# Hardwiring.net
KiCad netlist of a schematic drawn in Altium Designer
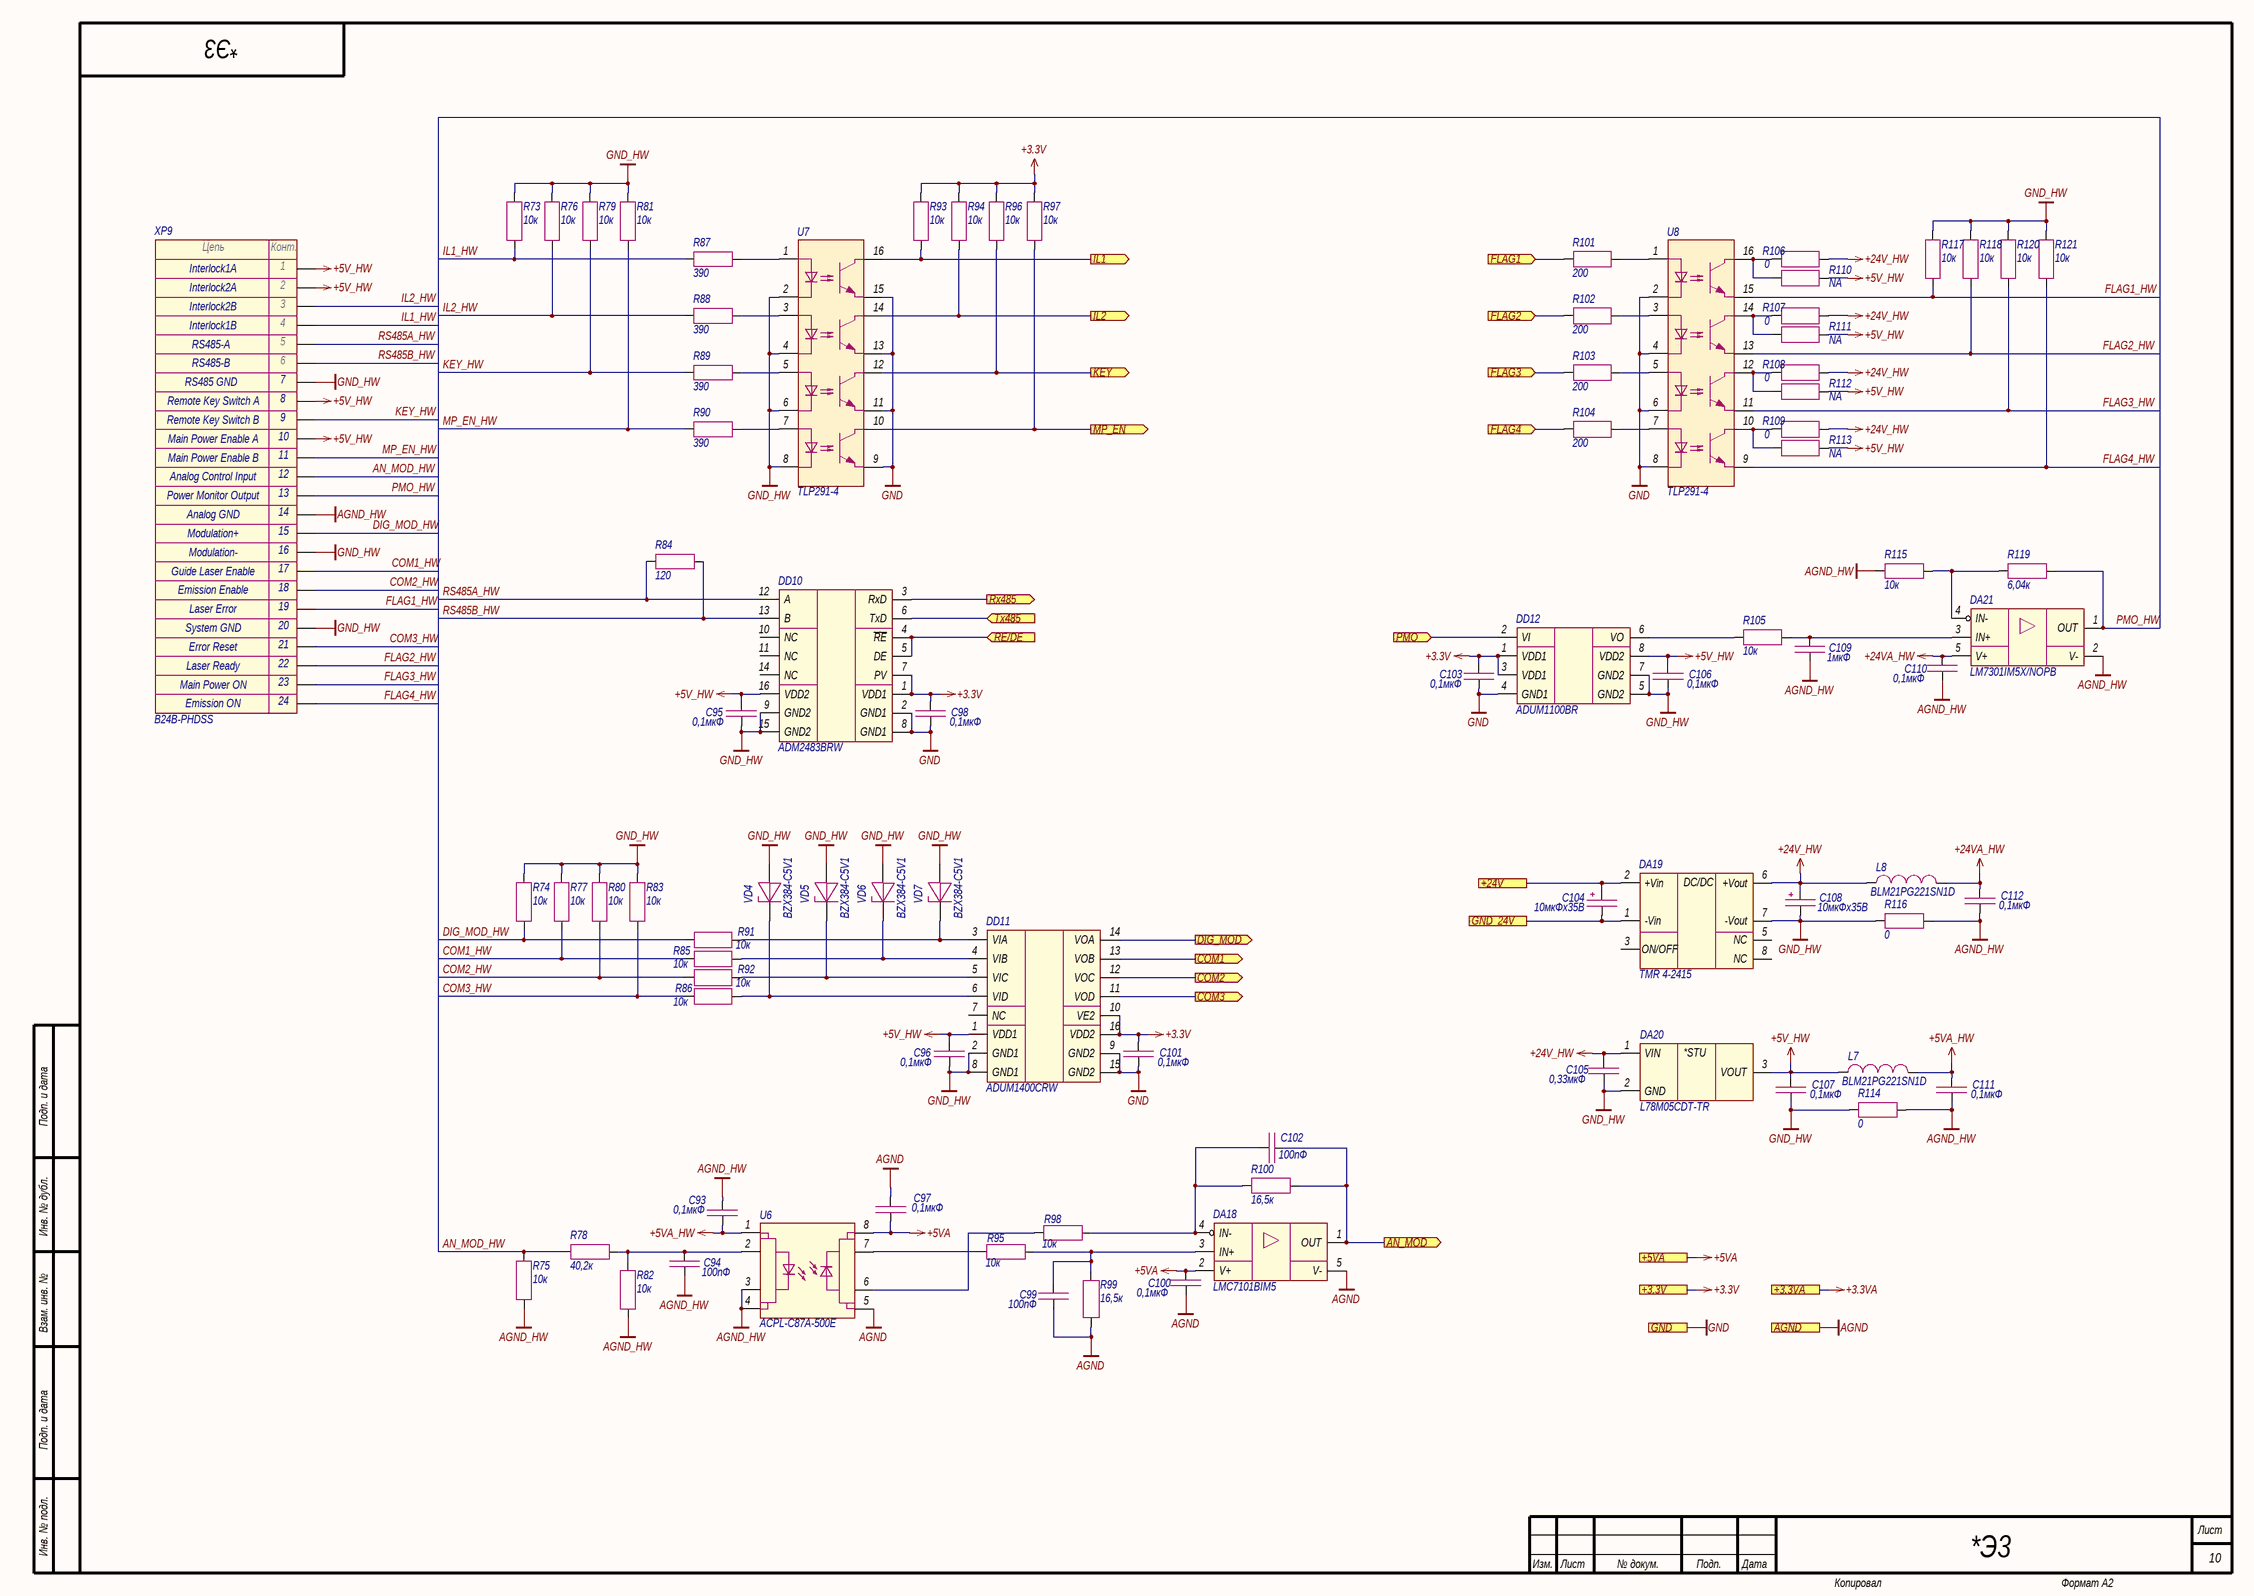
[diagram p0: Hardwiring.SchDoc]

(export (version "E")
  (design (tool "Eeschema 10.0.6"))
  (components
    (comp (ref "C93")
      (value "0,1мкФ")
      (footprint "Pcb_library:CAP_0603")
      (fields (field (name "MANUFACTURER") "Murata"))
      (libsource (lib "Schem_library") (part "Capacitor"))
    )
    (comp (ref "C94")
      (value "100пФ")
      (footprint "Pcb_library:CAP_0603")
      (fields (field (name "MANUFACTURER") "Murata"))
      (libsource (lib "Schem_library") (part "Capacitor"))
    )
    (comp (ref "C95")
      (value "0,1мкФ")
      (footprint "Pcb_library:CAP_0603")
      (fields (field (name "MANUFACTURER") "Murata"))
      (libsource (lib "Schem_library") (part "Capacitor"))
    )
    (comp (ref "C96")
      (value "0,1мкФ")
      (footprint "Pcb_library:CAP_0603")
      (fields (field (name "MANUFACTURER") "Murata"))
      (libsource (lib "Schem_library") (part "Capacitor"))
    )
    (comp (ref "C97")
      (value "0,1мкФ")
      (footprint "Pcb_library:CAP_0603")
      (fields (field (name "MANUFACTURER") "Murata"))
      (libsource (lib "Schem_library") (part "Capacitor"))
    )
    (comp (ref "C98")
      (value "0,1мкФ")
      (footprint "Pcb_library:CAP_0603")
      (fields (field (name "MANUFACTURER") "Murata"))
      (libsource (lib "Schem_library") (part "Capacitor"))
    )
    (comp (ref "C99")
      (value "100пФ")
      (footprint "Pcb_library:CAP_0603")
      (fields (field (name "MANUFACTURER") "Murata"))
      (libsource (lib "Schem_library") (part "Capacitor"))
    )
    (comp (ref "C100")
      (value "0,1мкФ")
      (footprint "Pcb_library:CAP_0603")
      (fields (field (name "MANUFACTURER") "Murata"))
      (libsource (lib "Schem_library") (part "Capacitor"))
    )
    (comp (ref "C101")
      (value "0,1мкФ")
      (footprint "Pcb_library:CAP_0603")
      (fields (field (name "MANUFACTURER") "Murata"))
      (libsource (lib "Schem_library") (part "Capacitor"))
    )
    (comp (ref "C102")
      (value "100пФ")
      (footprint "Pcb_library:CAP_0603")
      (fields (field (name "MANUFACTURER") "Murata"))
      (libsource (lib "Schem_library") (part "Capacitor"))
    )
    (comp (ref "C103")
      (value "0,1мкФ")
      (footprint "Pcb_library:CAP_0603")
      (fields (field (name "MANUFACTURER") "Murata"))
      (libsource (lib "Schem_library") (part "Capacitor"))
    )
    (comp (ref "C104")
      (value "10мкФх35B")
      (footprint "Pcb_library:CAP_C")
      (libsource (lib "") (part "Capacitor_Polar_1"))
    )
    (comp (ref "C105")
      (value "0,33мкФ")
      (footprint "Pcb_library:CAP_0805")
      (fields (field (name "MANUFACTURER") "Murata"))
      (libsource (lib "Schem_library") (part "Capacitor"))
    )
    (comp (ref "C106")
      (value "0,1мкФ")
      (footprint "Pcb_library:CAP_0603")
      (fields (field (name "MANUFACTURER") "Murata"))
      (libsource (lib "Schem_library") (part "Capacitor"))
    )
    (comp (ref "C107")
      (value "0,1мкФ")
      (footprint "Pcb_library:CAP_0603")
      (fields (field (name "MANUFACTURER") "Murata"))
      (libsource (lib "Schem_library") (part "Capacitor"))
    )
    (comp (ref "C108")
      (value "10мкФх35B")
      (footprint "Pcb_library:CAP_C")
      (libsource (lib "Schem_library") (part "Capacitor_Polar"))
    )
    (comp (ref "C109")
      (value "1мкФ")
      (footprint "Pcb_library:CAP_0603")
      (fields (field (name "MANUFACTURER") "Murata"))
      (libsource (lib "Schem_library") (part "Capacitor"))
    )
    (comp (ref "C110")
      (value "0,1мкФ")
      (footprint "Pcb_library:CAP_0603")
      (fields (field (name "MANUFACTURER") "Murata"))
      (libsource (lib "Schem_library") (part "Capacitor"))
    )
    (comp (ref "C111")
      (value "0,1мкФ")
      (footprint "Pcb_library:CAP_0603")
      (fields (field (name "MANUFACTURER") "Murata"))
      (libsource (lib "Schem_library") (part "Capacitor"))
    )
    (comp (ref "C112")
      (value "0,1мкФ")
      (footprint "Pcb_library:CAP_0603")
      (fields (field (name "MANUFACTURER") "Murata"))
      (libsource (lib "Schem_library") (part "Capacitor"))
    )
    (comp (ref "DA18")
      (value "LMC7101BIM5")
      (footprint "Pcb_library:SOT-23-5")
      (fields (field (name "MANUFACTURER") "Texas Instruments"))
      (libsource (lib "Schem_library") (part "LMC7101"))
    )
    (comp (ref "DA19")
      (value "TMR 4-2415")
      (footprint "Pcb_library:TMR4 (SIP-8)")
      (fields (field (name "MANUFACTURER") "Traco Power"))
      (libsource (lib "Schem_library") (part "TMR4"))
    )
    (comp (ref "DA20")
      (value "L78M05CDT-TR")
      (footprint "Pcb_library:TO-252")
      (fields (field (name "MANUFACTURER") "STMicroelectronics"))
      (libsource (lib "Schem_library") (part "L78M"))
    )
    (comp (ref "DA21")
      (value "LM7301IM5X/NOPB")
      (footprint "Pcb_library:SOT-23-5")
      (fields (field (name "MANUFACTURER") "Texas Instruments"))
      (libsource (lib "Schem_library") (part "LM7301IM5"))
    )
    (comp (ref "DD10")
      (value "ADM2483BRW")
      (footprint "Pcb_library:SOIC-16W")
      (fields (field (name "MANUFACTURER") "Analog Devices"))
      (libsource (lib "Schem_library") (part "ADM2483BRW"))
    )
    (comp (ref "DD11")
      (value "ADUM1400CRW")
      (footprint "Pcb_library:SOIC-16W")
      (fields (field (name "MANUFACTURER") "Analog Devices"))
      (libsource (lib "Schem_library") (part "ADUM1400"))
    )
    (comp (ref "DD12")
      (value "ADUM1100BR")
      (footprint "Pcb_library:SOIC-8")
      (fields (field (name "MANUFACTURER") "Analog Devices"))
      (libsource (lib "Schem_library") (part "ADUM1100"))
    )
    (comp (ref "L7")
      (value "BLM21PG221SN1D")
      (footprint "Pcb_library:IND_0805")
      (fields (field (name "MANUFACTURER") "Murata"))
      (libsource (lib "Schem_library") (part "Inductor"))
    )
    (comp (ref "L8")
      (value "BLM21PG221SN1D")
      (footprint "Pcb_library:IND_0805")
      (fields (field (name "MANUFACTURER") "Murata"))
      (libsource (lib "Schem_library") (part "Inductor"))
    )
    (comp (ref "R73")
      (value "10к")
      (footprint "Pcb_library:RES_0603")
      (fields (field (name "MANUFACTURER") "Yageo"))
      (libsource (lib "Schem_library") (part "Resistor"))
    )
    (comp (ref "R74")
      (value "10к")
      (footprint "Pcb_library:RES_0603")
      (fields (field (name "MANUFACTURER") "Yageo"))
      (libsource (lib "Schem_library") (part "Resistor"))
    )
    (comp (ref "R75")
      (value "10к")
      (footprint "Pcb_library:RES_0603")
      (fields (field (name "MANUFACTURER") "Yageo"))
      (libsource (lib "Schem_library") (part "Resistor"))
    )
    (comp (ref "R76")
      (value "10к")
      (footprint "Pcb_library:RES_0603")
      (fields (field (name "MANUFACTURER") "Yageo"))
      (libsource (lib "Schem_library") (part "Resistor"))
    )
    (comp (ref "R77")
      (value "10к")
      (footprint "Pcb_library:RES_0603")
      (fields (field (name "MANUFACTURER") "Yageo"))
      (libsource (lib "Schem_library") (part "Resistor"))
    )
    (comp (ref "R78")
      (value "40,2к")
      (footprint "Pcb_library:RES_0603")
      (fields (field (name "MANUFACTURER") "Yageo"))
      (libsource (lib "Schem_library") (part "Resistor"))
    )
    (comp (ref "R79")
      (value "10к")
      (footprint "Pcb_library:RES_0603")
      (fields (field (name "MANUFACTURER") "Yageo"))
      (libsource (lib "Schem_library") (part "Resistor"))
    )
    (comp (ref "R80")
      (value "10к")
      (footprint "Pcb_library:RES_0603")
      (fields (field (name "MANUFACTURER") "Yageo"))
      (libsource (lib "Schem_library") (part "Resistor"))
    )
    (comp (ref "R81")
      (value "10к")
      (footprint "Pcb_library:RES_0603")
      (fields (field (name "MANUFACTURER") "Yageo"))
      (libsource (lib "Schem_library") (part "Resistor"))
    )
    (comp (ref "R82")
      (value "10к")
      (footprint "Pcb_library:RES_0603")
      (fields (field (name "MANUFACTURER") "Yageo"))
      (libsource (lib "Schem_library") (part "Resistor"))
    )
    (comp (ref "R83")
      (value "10к")
      (footprint "Pcb_library:RES_0603")
      (fields (field (name "MANUFACTURER") "Yageo"))
      (libsource (lib "Schem_library") (part "Resistor"))
    )
    (comp (ref "R84")
      (value "120")
      (footprint "Pcb_library:RES_0805")
      (fields (field (name "MANUFACTURER") "Yageo"))
      (libsource (lib "Schem_library") (part "Resistor"))
    )
    (comp (ref "R85")
      (value "10к")
      (footprint "Pcb_library:RES_0603")
      (fields (field (name "MANUFACTURER") "Yageo"))
      (libsource (lib "Schem_library") (part "Resistor"))
    )
    (comp (ref "R86")
      (value "10к")
      (footprint "Pcb_library:RES_0603")
      (fields (field (name "MANUFACTURER") "Yageo"))
      (libsource (lib "Schem_library") (part "Resistor"))
    )
    (comp (ref "R87")
      (value "390")
      (footprint "Pcb_library:RES_0603")
      (fields (field (name "MANUFACTURER") "Yageo"))
      (libsource (lib "Schem_library") (part "Resistor"))
    )
    (comp (ref "R88")
      (value "390")
      (footprint "Pcb_library:RES_0603")
      (fields (field (name "MANUFACTURER") "Yageo"))
      (libsource (lib "Schem_library") (part "Resistor"))
    )
    (comp (ref "R89")
      (value "390")
      (footprint "Pcb_library:RES_0603")
      (fields (field (name "MANUFACTURER") "Yageo"))
      (libsource (lib "Schem_library") (part "Resistor"))
    )
    (comp (ref "R90")
      (value "390")
      (footprint "Pcb_library:RES_0603")
      (fields (field (name "MANUFACTURER") "Yageo"))
      (libsource (lib "Schem_library") (part "Resistor"))
    )
    (comp (ref "R91")
      (value "10к")
      (footprint "Pcb_library:RES_0603")
      (fields (field (name "MANUFACTURER") "Yageo"))
      (libsource (lib "Schem_library") (part "Resistor"))
    )
    (comp (ref "R92")
      (value "10к")
      (footprint "Pcb_library:RES_0603")
      (fields (field (name "MANUFACTURER") "Yageo"))
      (libsource (lib "Schem_library") (part "Resistor"))
    )
    (comp (ref "R93")
      (value "10к")
      (footprint "Pcb_library:RES_0603")
      (fields (field (name "MANUFACTURER") "Yageo"))
      (libsource (lib "Schem_library") (part "Resistor"))
    )
    (comp (ref "R94")
      (value "10к")
      (footprint "Pcb_library:RES_0603")
      (fields (field (name "MANUFACTURER") "Yageo"))
      (libsource (lib "Schem_library") (part "Resistor"))
    )
    (comp (ref "R95")
      (value "10к")
      (footprint "Pcb_library:RES_0603")
      (fields (field (name "MANUFACTURER") "Yageo"))
      (libsource (lib "Schem_library") (part "Resistor"))
    )
    (comp (ref "R96")
      (value "10к")
      (footprint "Pcb_library:RES_0603")
      (fields (field (name "MANUFACTURER") "Yageo"))
      (libsource (lib "Schem_library") (part "Resistor"))
    )
    (comp (ref "R97")
      (value "10к")
      (footprint "Pcb_library:RES_0603")
      (fields (field (name "MANUFACTURER") "Yageo"))
      (libsource (lib "Schem_library") (part "Resistor"))
    )
    (comp (ref "R98")
      (value "10к")
      (footprint "Pcb_library:RES_0603")
      (fields (field (name "MANUFACTURER") "Yageo"))
      (libsource (lib "Schem_library") (part "Resistor"))
    )
    (comp (ref "R99")
      (value "16,5к")
      (footprint "Pcb_library:RES_0603")
      (fields (field (name "MANUFACTURER") "Yageo"))
      (libsource (lib "Schem_library") (part "Resistor"))
    )
    (comp (ref "R100")
      (value "16,5к")
      (footprint "Pcb_library:RES_0603")
      (fields (field (name "MANUFACTURER") "Yageo"))
      (libsource (lib "Schem_library") (part "Resistor"))
    )
    (comp (ref "R101")
      (value "200")
      (footprint "Pcb_library:RES_0603")
      (fields (field (name "MANUFACTURER") "Yageo"))
      (libsource (lib "Schem_library") (part "Resistor"))
    )
    (comp (ref "R102")
      (value "200")
      (footprint "Pcb_library:RES_0603")
      (fields (field (name "MANUFACTURER") "Yageo"))
      (libsource (lib "Schem_library") (part "Resistor"))
    )
    (comp (ref "R103")
      (value "200")
      (footprint "Pcb_library:RES_0603")
      (fields (field (name "MANUFACTURER") "Yageo"))
      (libsource (lib "Schem_library") (part "Resistor"))
    )
    (comp (ref "R104")
      (value "200")
      (footprint "Pcb_library:RES_0603")
      (fields (field (name "MANUFACTURER") "Yageo"))
      (libsource (lib "Schem_library") (part "Resistor"))
    )
    (comp (ref "R105")
      (value "10к")
      (footprint "Pcb_library:RES_0603")
      (fields (field (name "MANUFACTURER") "Yageo"))
      (libsource (lib "Schem_library") (part "Resistor"))
    )
    (comp (ref "R106")
      (value "0")
      (footprint "Pcb_library:RES_0603")
      (fields (field (name "MANUFACTURER") "Yageo"))
      (libsource (lib "Schem_library") (part "Resistor"))
    )
    (comp (ref "R107")
      (value "0")
      (footprint "Pcb_library:RES_0603")
      (fields (field (name "MANUFACTURER") "Yageo"))
      (libsource (lib "Schem_library") (part "Resistor"))
    )
    (comp (ref "R108")
      (value "0")
      (footprint "Pcb_library:RES_0603")
      (fields (field (name "MANUFACTURER") "Yageo"))
      (libsource (lib "Schem_library") (part "Resistor"))
    )
    (comp (ref "R109")
      (value "0")
      (footprint "Pcb_library:RES_0603")
      (fields (field (name "MANUFACTURER") "Yageo"))
      (libsource (lib "Schem_library") (part "Resistor"))
    )
    (comp (ref "R110")
      (value "NA")
      (footprint "Pcb_library:RES_0603")
      (libsource (lib "Schem_library") (part "Resistor"))
    )
    (comp (ref "R111")
      (value "NA")
      (footprint "Pcb_library:RES_0603")
      (libsource (lib "Schem_library") (part "Resistor"))
    )
    (comp (ref "R112")
      (value "NA")
      (footprint "Pcb_library:RES_0603")
      (libsource (lib "Schem_library") (part "Resistor"))
    )
    (comp (ref "R113")
      (value "NA")
      (footprint "Pcb_library:RES_0603")
      (libsource (lib "Schem_library") (part "Resistor"))
    )
    (comp (ref "R114")
      (value "0")
      (footprint "Pcb_library:RES_0805")
      (fields (field (name "MANUFACTURER") "Yageo"))
      (libsource (lib "Schem_library") (part "Resistor"))
    )
    (comp (ref "R115")
      (value "10к")
      (footprint "Pcb_library:RES_0603")
      (fields (field (name "MANUFACTURER") "Yageo"))
      (libsource (lib "Schem_library") (part "Resistor"))
    )
    (comp (ref "R116")
      (value "0")
      (footprint "Pcb_library:RES_0805")
      (fields (field (name "MANUFACTURER") "Yageo"))
      (libsource (lib "Schem_library") (part "Resistor"))
    )
    (comp (ref "R117")
      (value "10к")
      (footprint "Pcb_library:RES_0603")
      (fields (field (name "MANUFACTURER") "Yageo"))
      (libsource (lib "Schem_library") (part "Resistor"))
    )
    (comp (ref "R118")
      (value "10к")
      (footprint "Pcb_library:RES_0603")
      (fields (field (name "MANUFACTURER") "Yageo"))
      (libsource (lib "Schem_library") (part "Resistor"))
    )
    (comp (ref "R119")
      (value "6,04к")
      (footprint "Pcb_library:RES_0603")
      (fields (field (name "MANUFACTURER") "Yageo"))
      (libsource (lib "Schem_library") (part "Resistor"))
    )
    (comp (ref "R120")
      (value "10к")
      (footprint "Pcb_library:RES_0603")
      (fields (field (name "MANUFACTURER") "Yageo"))
      (libsource (lib "Schem_library") (part "Resistor"))
    )
    (comp (ref "R121")
      (value "10к")
      (footprint "Pcb_library:RES_0603")
      (fields (field (name "MANUFACTURER") "Yageo"))
      (libsource (lib "Schem_library") (part "Resistor"))
    )
    (comp (ref "U6")
      (value "ACPL-C87A-500E")
      (footprint "Pcb_library:SSO-8")
      (fields (field (name "MANUFACTURER") "Broadcom"))
      (libsource (lib "Schem_library") (part "ACPL-C87"))
    )
    (comp (ref "U7")
      (value "TLP291-4")
      (footprint "Pcb_library:SOP-16")
      (fields (field (name "MANUFACTURER") "Toshiba"))
      (libsource (lib "Schem_library") (part "TLP281-4"))
    )
    (comp (ref "U8")
      (value "TLP291-4")
      (footprint "Pcb_library:SOP-16")
      (fields (field (name "MANUFACTURER") "Toshiba"))
      (libsource (lib "Schem_library") (part "TLP281-4"))
    )
    (comp (ref "VD4")
      (value "BZX384-C5V1")
      (footprint "Pcb_library:SOD-323")
      (fields (field (name "MANUFACTURER") "Nexperia"))
      (libsource (lib "Schem_library") (part "Diode_Zener"))
    )
    (comp (ref "VD5")
      (value "BZX384-C5V1")
      (footprint "Pcb_library:SOD-323")
      (fields (field (name "MANUFACTURER") "Nexperia"))
      (libsource (lib "Schem_library") (part "Diode_Zener"))
    )
    (comp (ref "VD6")
      (value "BZX384-C5V1")
      (footprint "Pcb_library:SOD-323")
      (fields (field (name "MANUFACTURER") "Nexperia"))
      (libsource (lib "Schem_library") (part "Diode_Zener"))
    )
    (comp (ref "VD7")
      (value "BZX384-C5V1")
      (footprint "Pcb_library:SOD-323")
      (fields (field (name "MANUFACTURER") "Nexperia"))
      (libsource (lib "Schem_library") (part "Diode_Zener"))
    )
    (comp (ref "XP9")
      (value "B24B-PHDSS")
      (footprint "Pcb_library:B24B-PHDSS")
      (fields (field (name "MANUFACTURER") "JST"))
      (libsource (lib "Schem_library") (part "Connector-24"))
    )
  )
  (nets
    (net (code "1") (name "+3.3V") (class "Default")
      (node (ref "C101") (pin "1") (pinfunction "1_1") (pintype "passive"))
      (node (ref "C103") (pin "1") (pinfunction "1_1") (pintype "passive"))
      (node (ref "C98") (pin "1") (pinfunction "1_1") (pintype "passive"))
      (node (ref "DD10") (pin "1") (pinfunction "VDD1_1") (pintype "passive"))
      (node (ref "DD10") (pin "7") (pinfunction "PV_7") (pintype "passive"))
      (node (ref "DD11") (pin "10") (pinfunction "VE2_10") (pintype "passive"))
      (node (ref "DD11") (pin "16") (pinfunction "VDD2_16") (pintype "passive"))
      (node (ref "DD12") (pin "1") (pinfunction "VDD1_1") (pintype "passive"))
      (node (ref "DD12") (pin "3") (pinfunction "VDD1_3") (pintype "passive"))
      (node (ref "R93") (pin "1") (pinfunction "1_1") (pintype "passive"))
      (node (ref "R94") (pin "1") (pinfunction "1_1") (pintype "passive"))
      (node (ref "R96") (pin "1") (pinfunction "1_1") (pintype "passive"))
      (node (ref "R97") (pin "1") (pinfunction "1_1") (pintype "passive"))
    )
    (net (code "3") (name "+5VA") (class "Default")
      (node (ref "C100") (pin "1") (pinfunction "1_1") (pintype "passive"))
      (node (ref "C97") (pin "1") (pinfunction "1_1") (pintype "passive"))
      (node (ref "DA18") (pin "2") (pinfunction "V+_2") (pintype "passive"))
      (node (ref "U6") (pin "8") (pinfunction "VDD2_8") (pintype "passive"))
    )
    (net (code "4") (name "+5VA_HW") (class "Default")
      (node (ref "C111") (pin "1") (pinfunction "1_1") (pintype "passive"))
      (node (ref "C93") (pin "1") (pinfunction "1_1") (pintype "passive"))
      (node (ref "L7") (pin "2") (pinfunction "2_2") (pintype "passive"))
      (node (ref "U6") (pin "1") (pinfunction "VDD1_1") (pintype "passive"))
    )
    (net (code "5") (name "+5V_HW") (class "Default")
      (node (ref "C106") (pin "1") (pinfunction "1_1") (pintype "passive"))
      (node (ref "C107") (pin "1") (pinfunction "1_1") (pintype "passive"))
      (node (ref "C95") (pin "1") (pinfunction "1_1") (pintype "passive"))
      (node (ref "C96") (pin "1") (pinfunction "1_1") (pintype "passive"))
      (node (ref "DA20") (pin "3") (pinfunction "VOUT_3") (pintype "passive"))
      (node (ref "DD10") (pin "16") (pinfunction "VDD2_16") (pintype "passive"))
      (node (ref "DD11") (pin "1") (pinfunction "VDD1_1") (pintype "passive"))
      (node (ref "DD12") (pin "8") (pinfunction "VDD2_8") (pintype "passive"))
      (node (ref "L7") (pin "1") (pinfunction "1_1") (pintype "passive"))
      (node (ref "R110") (pin "2") (pinfunction "2_2") (pintype "passive"))
      (node (ref "R111") (pin "2") (pinfunction "2_2") (pintype "passive"))
      (node (ref "R112") (pin "2") (pinfunction "2_2") (pintype "passive"))
      (node (ref "R113") (pin "2") (pinfunction "2_2") (pintype "passive"))
      (node (ref "XP9") (pin "1") (pintype "passive"))
      (node (ref "XP9") (pin "10") (pintype "passive"))
      (node (ref "XP9") (pin "2") (pintype "passive"))
      (node (ref "XP9") (pin "8") (pintype "passive"))
    )
    (net (code "6") (name "+24VA_HW") (class "Default")
      (node (ref "C110") (pin "1") (pinfunction "1_1") (pintype "passive"))
      (node (ref "C112") (pin "1") (pinfunction "1_1") (pintype "passive"))
      (node (ref "DA21") (pin "5") (pinfunction "V+_5") (pintype "passive"))
      (node (ref "L8") (pin "2") (pinfunction "2_2") (pintype "passive"))
    )
    (net (code "7") (name "+24V_HW") (class "Default")
      (node (ref "C105") (pin "2") (pinfunction "2_2") (pintype "passive"))
      (node (ref "C108") (pin "1") (pinfunction "1_1") (pintype "passive"))
      (node (ref "DA19") (pin "6") (pinfunction "+Vout_6") (pintype "passive"))
      (node (ref "DA20") (pin "1") (pinfunction "VIN_1") (pintype "passive"))
      (node (ref "L8") (pin "1") (pinfunction "1_1") (pintype "passive"))
      (node (ref "R106") (pin "2") (pinfunction "2_2") (pintype "passive"))
      (node (ref "R107") (pin "2") (pinfunction "2_2") (pintype "passive"))
      (node (ref "R108") (pin "2") (pinfunction "2_2") (pintype "passive"))
      (node (ref "R109") (pin "2") (pinfunction "2_2") (pintype "passive"))
    )
    (net (code "8") (name "/+24V") (class "Default")
      (node (ref "C104") (pin "1") (pinfunction "1_1") (pintype "passive"))
      (node (ref "DA19") (pin "2") (pinfunction "+Vin_2") (pintype "passive"))
    )
    (net (code "9") (name "/AN_MOD") (class "Default")
      (node (ref "C102") (pin "2") (pinfunction "2_2") (pintype "passive"))
      (node (ref "DA18") (pin "1") (pinfunction "OUT_1") (pintype "passive"))
      (node (ref "R100") (pin "1") (pinfunction "1_1") (pintype "passive"))
    )
    (net (code "10") (name "/AN_MOD_HW") (class "Default")
      (node (ref "R75") (pin "1") (pinfunction "1_1") (pintype "passive"))
      (node (ref "R78") (pin "2") (pinfunction "2_2") (pintype "passive"))
      (node (ref "XP9") (pin "12") (pintype "passive"))
    )
    (net (code "11") (name "/COM1") (class "Default")
      (node (ref "DD11") (pin "13") (pinfunction "VOB_13") (pintype "passive"))
    )
    (net (code "12") (name "/COM1_HW") (class "Default")
      (node (ref "R77") (pin "2") (pinfunction "2_2") (pintype "passive"))
      (node (ref "R85") (pin "1") (pinfunction "1_1") (pintype "passive"))
      (node (ref "XP9") (pin "17") (pintype "passive"))
    )
    (net (code "13") (name "/COM2") (class "Default")
      (node (ref "DD11") (pin "12") (pinfunction "VOC_12") (pintype "passive"))
    )
    (net (code "14") (name "/COM2_HW") (class "Default")
      (node (ref "R80") (pin "2") (pinfunction "2_2") (pintype "passive"))
      (node (ref "R92") (pin "1") (pinfunction "1_1") (pintype "passive"))
      (node (ref "XP9") (pin "18") (pintype "passive"))
    )
    (net (code "15") (name "/COM3") (class "Default")
      (node (ref "DD11") (pin "11") (pinfunction "VOD_11") (pintype "passive"))
    )
    (net (code "16") (name "/COM3_HW") (class "Default")
      (node (ref "R83") (pin "2") (pinfunction "2_2") (pintype "passive"))
      (node (ref "R86") (pin "1") (pinfunction "1_1") (pintype "passive"))
      (node (ref "XP9") (pin "21") (pintype "passive"))
    )
    (net (code "17") (name "/DIG_MOD") (class "Default")
      (node (ref "DD11") (pin "14") (pinfunction "VOA_14") (pintype "passive"))
    )
    (net (code "18") (name "/DIG_MOD_HW") (class "Default")
      (node (ref "R74") (pin "2") (pinfunction "2_2") (pintype "passive"))
      (node (ref "R91") (pin "1") (pinfunction "1_1") (pintype "passive"))
      (node (ref "XP9") (pin "15") (pintype "passive"))
    )
    (net (code "19") (name "/FLAG1") (class "Default")
      (node (ref "R101") (pin "2") (pinfunction "2_2") (pintype "passive"))
    )
    (net (code "20") (name "/FLAG1_HW") (class "Default")
      (node (ref "R117") (pin "2") (pinfunction "2_2") (pintype "passive"))
      (node (ref "U8") (pin "15") (pintype "passive"))
      (node (ref "XP9") (pin "19") (pintype "passive"))
    )
    (net (code "21") (name "/FLAG2") (class "Default")
      (node (ref "R102") (pin "2") (pinfunction "2_2") (pintype "passive"))
    )
    (net (code "22") (name "/FLAG2_HW") (class "Default")
      (node (ref "R118") (pin "2") (pinfunction "2_2") (pintype "passive"))
      (node (ref "U8") (pin "13") (pintype "passive"))
      (node (ref "XP9") (pin "22") (pintype "passive"))
    )
    (net (code "23") (name "/FLAG3") (class "Default")
      (node (ref "R103") (pin "2") (pinfunction "2_2") (pintype "passive"))
    )
    (net (code "24") (name "/FLAG3_HW") (class "Default")
      (node (ref "R120") (pin "2") (pinfunction "2_2") (pintype "passive"))
      (node (ref "U8") (pin "11") (pintype "passive"))
      (node (ref "XP9") (pin "23") (pintype "passive"))
    )
    (net (code "25") (name "/FLAG4") (class "Default")
      (node (ref "R104") (pin "2") (pinfunction "2_2") (pintype "passive"))
    )
    (net (code "26") (name "/FLAG4_HW") (class "Default")
      (node (ref "R121") (pin "2") (pinfunction "2_2") (pintype "passive"))
      (node (ref "U8") (pin "9") (pintype "passive"))
      (node (ref "XP9") (pin "24") (pintype "passive"))
    )
    (net (code "27") (name "/GND_24V") (class "Default")
      (node (ref "C104") (pin "2") (pinfunction "2_2") (pintype "passive"))
      (node (ref "DA19") (pin "1") (pinfunction "-Vin_1") (pintype "passive"))
    )
    (net (code "28") (name "/IL1") (class "Default")
      (node (ref "R93") (pin "2") (pinfunction "2_2") (pintype "passive"))
      (node (ref "U7") (pin "16") (pintype "passive"))
    )
    (net (code "29") (name "/IL1_HW") (class "Default")
      (node (ref "R73") (pin "2") (pinfunction "2_2") (pintype "passive"))
      (node (ref "R87") (pin "1") (pinfunction "1_1") (pintype "passive"))
      (node (ref "XP9") (pin "4") (pintype "passive"))
    )
    (net (code "30") (name "/IL2") (class "Default")
      (node (ref "R94") (pin "2") (pinfunction "2_2") (pintype "passive"))
      (node (ref "U7") (pin "14") (pintype "passive"))
    )
    (net (code "31") (name "/IL2_HW") (class "Default")
      (node (ref "R76") (pin "2") (pinfunction "2_2") (pintype "passive"))
      (node (ref "R88") (pin "1") (pinfunction "1_1") (pintype "passive"))
      (node (ref "XP9") (pin "3") (pintype "passive"))
    )
    (net (code "32") (name "/KEY") (class "Default")
      (node (ref "R96") (pin "2") (pinfunction "2_2") (pintype "passive"))
      (node (ref "U7") (pin "12") (pintype "passive"))
    )
    (net (code "33") (name "/KEY_HW") (class "Default")
      (node (ref "R79") (pin "2") (pinfunction "2_2") (pintype "passive"))
      (node (ref "R89") (pin "1") (pinfunction "1_1") (pintype "passive"))
      (node (ref "XP9") (pin "9") (pintype "passive"))
    )
    (net (code "34") (name "/MP_EN") (class "Default")
      (node (ref "R97") (pin "2") (pinfunction "2_2") (pintype "passive"))
      (node (ref "U7") (pin "10") (pintype "passive"))
    )
    (net (code "35") (name "/MP_EN_HW") (class "Default")
      (node (ref "R81") (pin "2") (pinfunction "2_2") (pintype "passive"))
      (node (ref "R90") (pin "1") (pinfunction "1_1") (pintype "passive"))
      (node (ref "XP9") (pin "11") (pintype "passive"))
    )
    (net (code "36") (name "/PMO") (class "Default")
      (node (ref "DD12") (pin "2") (pinfunction "VI_2") (pintype "passive"))
    )
    (net (code "37") (name "/PMO_HW") (class "Default")
      (node (ref "DA21") (pin "1") (pinfunction "OUT_1") (pintype "passive"))
      (node (ref "R119") (pin "2") (pinfunction "2_2") (pintype "passive"))
      (node (ref "XP9") (pin "13") (pintype "passive"))
    )
    (net (code "38") (name "/RE{slash}DE") (class "Default")
      (node (ref "DD10") (pin "4") (pinfunction "~{RE}_4") (pintype "passive"))
      (node (ref "DD10") (pin "5") (pinfunction "DE_5") (pintype "passive"))
    )
    (net (code "39") (name "/RS485A_HW") (class "Default")
      (node (ref "DD10") (pin "12") (pinfunction "A_12") (pintype "passive"))
      (node (ref "R84") (pin "1") (pinfunction "1_1") (pintype "passive"))
      (node (ref "XP9") (pin "5") (pintype "passive"))
    )
    (net (code "40") (name "/RS485B_HW") (class "Default")
      (node (ref "DD10") (pin "13") (pinfunction "B_13") (pintype "passive"))
      (node (ref "R84") (pin "2") (pinfunction "2_2") (pintype "passive"))
      (node (ref "XP9") (pin "6") (pintype "passive"))
    )
    (net (code "41") (name "/Rx485") (class "Default")
      (node (ref "DD10") (pin "3") (pinfunction "RxD_3") (pintype "passive"))
    )
    (net (code "42") (name "/Tx485") (class "Default")
      (node (ref "DD10") (pin "6") (pinfunction "TxD_6") (pintype "passive"))
    )
    (net (code "43") (name "AGND") (class "Default")
      (node (ref "C100") (pin "2") (pinfunction "2_2") (pintype "passive"))
      (node (ref "C97") (pin "2") (pinfunction "2_2") (pintype "passive"))
      (node (ref "C99") (pin "2") (pinfunction "2_2") (pintype "passive"))
      (node (ref "DA18") (pin "5") (pinfunction "V-_5") (pintype "passive"))
      (node (ref "R99") (pin "2") (pinfunction "2_2") (pintype "passive"))
      (node (ref "U6") (pin "5") (pinfunction "GND2_5") (pintype "passive"))
    )
    (net (code "44") (name "AGND_HW") (class "Default")
      (node (ref "C109") (pin "2") (pinfunction "2_2") (pintype "passive"))
      (node (ref "C110") (pin "2") (pinfunction "2_2") (pintype "passive"))
      (node (ref "C111") (pin "2") (pinfunction "2_2") (pintype "passive"))
      (node (ref "C112") (pin "2") (pinfunction "2_2") (pintype "passive"))
      (node (ref "C93") (pin "2") (pinfunction "2_2") (pintype "passive"))
      (node (ref "C94") (pin "1") (pinfunction "1_1") (pintype "passive"))
      (node (ref "DA21") (pin "2") (pinfunction "V-_2") (pintype "passive"))
      (node (ref "R114") (pin "2") (pinfunction "2_2") (pintype "passive"))
      (node (ref "R115") (pin "1") (pinfunction "1_1") (pintype "passive"))
      (node (ref "R116") (pin "2") (pinfunction "2_2") (pintype "passive"))
      (node (ref "R75") (pin "2") (pinfunction "2_2") (pintype "passive"))
      (node (ref "R82") (pin "2") (pinfunction "2_2") (pintype "passive"))
      (node (ref "U6") (pin "3") (pinfunction "SHDN_3") (pintype "passive"))
      (node (ref "U6") (pin "4") (pinfunction "GND1_4") (pintype "passive"))
      (node (ref "XP9") (pin "14") (pintype "passive"))
    )
    (net (code "45") (name "GND") (class "Default")
      (node (ref "C101") (pin "2") (pinfunction "2_2") (pintype "passive"))
      (node (ref "C103") (pin "2") (pinfunction "2_2") (pintype "passive"))
      (node (ref "C98") (pin "2") (pinfunction "2_2") (pintype "passive"))
      (node (ref "DD10") (pin "2") (pinfunction "GND1_2") (pintype "passive"))
      (node (ref "DD10") (pin "8") (pinfunction "GND1_8") (pintype "passive"))
      (node (ref "DD11") (pin "15") (pinfunction "GND2_15") (pintype "passive"))
      (node (ref "DD11") (pin "9") (pinfunction "GND2_9") (pintype "passive"))
      (node (ref "DD12") (pin "4") (pinfunction "GND1_4") (pintype "passive"))
      (node (ref "U7") (pin "11") (pintype "passive"))
      (node (ref "U7") (pin "13") (pintype "passive"))
      (node (ref "U7") (pin "15") (pintype "passive"))
      (node (ref "U7") (pin "9") (pintype "passive"))
      (node (ref "U8") (pin "2") (pintype "passive"))
      (node (ref "U8") (pin "4") (pintype "passive"))
      (node (ref "U8") (pin "6") (pintype "passive"))
      (node (ref "U8") (pin "8") (pintype "passive"))
    )
    (net (code "46") (name "GND_HW") (class "Default")
      (node (ref "C105") (pin "1") (pinfunction "1_1") (pintype "passive"))
      (node (ref "C106") (pin "2") (pinfunction "2_2") (pintype "passive"))
      (node (ref "C107") (pin "2") (pinfunction "2_2") (pintype "passive"))
      (node (ref "C108") (pin "2") (pinfunction "2_2") (pintype "passive"))
      (node (ref "C95") (pin "2") (pinfunction "2_2") (pintype "passive"))
      (node (ref "C96") (pin "2") (pinfunction "2_2") (pintype "passive"))
      (node (ref "DA19") (pin "7") (pinfunction "-Vout_7") (pintype "passive"))
      (node (ref "DA20") (pin "2") (pinfunction "GND_2") (pintype "passive"))
      (node (ref "DD10") (pin "15") (pinfunction "GND2_15") (pintype "passive"))
      (node (ref "DD10") (pin "9") (pinfunction "GND2_9") (pintype "passive"))
      (node (ref "DD11") (pin "2") (pinfunction "GND1_2") (pintype "passive"))
      (node (ref "DD11") (pin "8") (pinfunction "GND1_8") (pintype "passive"))
      (node (ref "DD12") (pin "5") (pinfunction "GND2_5") (pintype "passive"))
      (node (ref "DD12") (pin "7") (pinfunction "GND2_7") (pintype "passive"))
      (node (ref "R114") (pin "1") (pinfunction "1_1") (pintype "passive"))
      (node (ref "R116") (pin "1") (pinfunction "1_1") (pintype "passive"))
      (node (ref "R117") (pin "1") (pinfunction "1_1") (pintype "passive"))
      (node (ref "R118") (pin "1") (pinfunction "1_1") (pintype "passive"))
      (node (ref "R120") (pin "1") (pinfunction "1_1") (pintype "passive"))
      (node (ref "R121") (pin "1") (pinfunction "1_1") (pintype "passive"))
      (node (ref "R73") (pin "1") (pinfunction "1_1") (pintype "passive"))
      (node (ref "R74") (pin "1") (pinfunction "1_1") (pintype "passive"))
      (node (ref "R76") (pin "1") (pinfunction "1_1") (pintype "passive"))
      (node (ref "R77") (pin "1") (pinfunction "1_1") (pintype "passive"))
      (node (ref "R79") (pin "1") (pinfunction "1_1") (pintype "passive"))
      (node (ref "R80") (pin "1") (pinfunction "1_1") (pintype "passive"))
      (node (ref "R81") (pin "1") (pinfunction "1_1") (pintype "passive"))
      (node (ref "R83") (pin "1") (pinfunction "1_1") (pintype "passive"))
      (node (ref "U7") (pin "2") (pintype "passive"))
      (node (ref "U7") (pin "4") (pintype "passive"))
      (node (ref "U7") (pin "6") (pintype "passive"))
      (node (ref "U7") (pin "8") (pintype "passive"))
      (node (ref "VD4") (pin "2") (pinfunction "A_2") (pintype "passive"))
      (node (ref "VD5") (pin "2") (pinfunction "A_2") (pintype "passive"))
      (node (ref "VD6") (pin "2") (pinfunction "A_2") (pintype "passive"))
      (node (ref "VD7") (pin "2") (pinfunction "A_2") (pintype "passive"))
      (node (ref "XP9") (pin "16") (pintype "passive"))
      (node (ref "XP9") (pin "20") (pintype "passive"))
      (node (ref "XP9") (pin "7") (pintype "passive"))
    )
    (net (code "47") (name "Net-(DA18-IN+)") (class "Default")
      (node (ref "C99") (pin "1") (pinfunction "1_1") (pintype "passive"))
      (node (ref "DA18") (pin "3") (pinfunction "IN+_3") (pintype "passive"))
      (node (ref "R95") (pin "2") (pinfunction "2_2") (pintype "passive"))
      (node (ref "R99") (pin "1") (pinfunction "1_1") (pintype "passive"))
    )
    (net (code "48") (name "Net-(DA18-IN-)") (class "Default")
      (node (ref "C102") (pin "1") (pinfunction "1_1") (pintype "passive"))
      (node (ref "DA18") (pin "4") (pinfunction "IN-_4") (pintype "passive"))
      (node (ref "R100") (pin "2") (pinfunction "2_2") (pintype "passive"))
      (node (ref "R98") (pin "2") (pinfunction "2_2") (pintype "passive"))
    )
    (net (code "49") (name "Net-(DA21-IN+)") (class "Default")
      (node (ref "C109") (pin "1") (pinfunction "1_1") (pintype "passive"))
      (node (ref "DA21") (pin "3") (pinfunction "IN+_3") (pintype "passive"))
      (node (ref "R105") (pin "2") (pinfunction "2_2") (pintype "passive"))
    )
    (net (code "50") (name "Net-(DA21-IN-)") (class "Default")
      (node (ref "DA21") (pin "4") (pinfunction "IN-_4") (pintype "passive"))
      (node (ref "R115") (pin "2") (pinfunction "2_2") (pintype "passive"))
      (node (ref "R119") (pin "1") (pinfunction "1_1") (pintype "passive"))
    )
    (net (code "51") (name "Net-(DD11-VIA)") (class "Default")
      (node (ref "DD11") (pin "3") (pinfunction "VIA_3") (pintype "passive"))
      (node (ref "R91") (pin "2") (pinfunction "2_2") (pintype "passive"))
      (node (ref "VD7") (pin "1") (pinfunction "K_1") (pintype "passive"))
    )
    (net (code "52") (name "Net-(DD11-VIB)") (class "Default")
      (node (ref "DD11") (pin "4") (pinfunction "VIB_4") (pintype "passive"))
      (node (ref "R85") (pin "2") (pinfunction "2_2") (pintype "passive"))
      (node (ref "VD6") (pin "1") (pinfunction "K_1") (pintype "passive"))
    )
    (net (code "53") (name "Net-(DD11-VIC)") (class "Default")
      (node (ref "DD11") (pin "5") (pinfunction "VIC_5") (pintype "passive"))
      (node (ref "R92") (pin "2") (pinfunction "2_2") (pintype "passive"))
      (node (ref "VD5") (pin "1") (pinfunction "K_1") (pintype "passive"))
    )
    (net (code "54") (name "Net-(DD11-VID)") (class "Default")
      (node (ref "DD11") (pin "6") (pinfunction "VID_6") (pintype "passive"))
      (node (ref "R86") (pin "2") (pinfunction "2_2") (pintype "passive"))
      (node (ref "VD4") (pin "1") (pinfunction "K_1") (pintype "passive"))
    )
    (net (code "55") (name "Net-(DD12-VO)") (class "Default")
      (node (ref "DD12") (pin "6") (pinfunction "VO_6") (pintype "passive"))
      (node (ref "R105") (pin "1") (pinfunction "1_1") (pintype "passive"))
    )
    (net (code "56") (name "Net-(R87-Pad2)") (class "Default")
      (node (ref "R87") (pin "2") (pinfunction "2_2") (pintype "passive"))
      (node (ref "U7") (pin "1") (pintype "passive"))
    )
    (net (code "57") (name "Net-(R88-Pad2)") (class "Default")
      (node (ref "R88") (pin "2") (pinfunction "2_2") (pintype "passive"))
      (node (ref "U7") (pin "3") (pintype "passive"))
    )
    (net (code "58") (name "Net-(R89-Pad2)") (class "Default")
      (node (ref "R89") (pin "2") (pinfunction "2_2") (pintype "passive"))
      (node (ref "U7") (pin "5") (pintype "passive"))
    )
    (net (code "59") (name "Net-(R90-Pad2)") (class "Default")
      (node (ref "R90") (pin "2") (pinfunction "2_2") (pintype "passive"))
      (node (ref "U7") (pin "7") (pintype "passive"))
    )
    (net (code "60") (name "Net-(R101-Pad1)") (class "Default")
      (node (ref "R101") (pin "1") (pinfunction "1_1") (pintype "passive"))
      (node (ref "U8") (pin "1") (pintype "passive"))
    )
    (net (code "61") (name "Net-(R102-Pad1)") (class "Default")
      (node (ref "R102") (pin "1") (pinfunction "1_1") (pintype "passive"))
      (node (ref "U8") (pin "3") (pintype "passive"))
    )
    (net (code "62") (name "Net-(R103-Pad1)") (class "Default")
      (node (ref "R103") (pin "1") (pinfunction "1_1") (pintype "passive"))
      (node (ref "U8") (pin "5") (pintype "passive"))
    )
    (net (code "63") (name "Net-(R104-Pad1)") (class "Default")
      (node (ref "R104") (pin "1") (pinfunction "1_1") (pintype "passive"))
      (node (ref "U8") (pin "7") (pintype "passive"))
    )
    (net (code "64") (name "Net-(R106-Pad1)") (class "Default")
      (node (ref "R106") (pin "1") (pinfunction "1_1") (pintype "passive"))
      (node (ref "R110") (pin "1") (pinfunction "1_1") (pintype "passive"))
      (node (ref "U8") (pin "16") (pintype "passive"))
    )
    (net (code "65") (name "Net-(R107-Pad1)") (class "Default")
      (node (ref "R107") (pin "1") (pinfunction "1_1") (pintype "passive"))
      (node (ref "R111") (pin "1") (pinfunction "1_1") (pintype "passive"))
      (node (ref "U8") (pin "14") (pintype "passive"))
    )
    (net (code "66") (name "Net-(R108-Pad1)") (class "Default")
      (node (ref "R108") (pin "1") (pinfunction "1_1") (pintype "passive"))
      (node (ref "R112") (pin "1") (pinfunction "1_1") (pintype "passive"))
      (node (ref "U8") (pin "12") (pintype "passive"))
    )
    (net (code "67") (name "Net-(R109-Pad1)") (class "Default")
      (node (ref "R109") (pin "1") (pinfunction "1_1") (pintype "passive"))
      (node (ref "R113") (pin "1") (pinfunction "1_1") (pintype "passive"))
      (node (ref "U8") (pin "10") (pintype "passive"))
    )
    (net (code "68") (name "Net-(U6-VIN)") (class "Default")
      (node (ref "C94") (pin "2") (pinfunction "2_2") (pintype "passive"))
      (node (ref "R78") (pin "1") (pinfunction "1_1") (pintype "passive"))
      (node (ref "R82") (pin "1") (pinfunction "1_1") (pintype "passive"))
      (node (ref "U6") (pin "2") (pinfunction "VIN_2") (pintype "passive"))
    )
    (net (code "69") (name "Net-(U6-VOUT+)") (class "Default")
      (node (ref "R95") (pin "1") (pinfunction "1_1") (pintype "passive"))
      (node (ref "U6") (pin "7") (pinfunction "VOUT+_7") (pintype "passive"))
    )
    (net (code "70") (name "Net-(U6-VOUT-)") (class "Default")
      (node (ref "R98") (pin "1") (pinfunction "1_1") (pintype "passive"))
      (node (ref "U6") (pin "6") (pinfunction "VOUT-_6") (pintype "passive"))
    )
    (net (code "71") (name "unconnected-(DA19-NC-Pad5)") (class "Default")
      (node (ref "DA19") (pin "5") (pinfunction "NC_5") (pintype "passive"))
    )
    (net (code "72") (name "unconnected-(DA19-NC-Pad8)") (class "Default")
      (node (ref "DA19") (pin "8") (pinfunction "NC_8") (pintype "passive"))
    )
    (net (code "73") (name "unconnected-(DA19-ON{slash}OFF-Pad3)") (class "Default")
      (node (ref "DA19") (pin "3") (pinfunction "ON/OFF_3") (pintype "passive"))
    )
    (net (code "74") (name "unconnected-(DD10-NC-Pad10)") (class "Default")
      (node (ref "DD10") (pin "10") (pinfunction "NC_10") (pintype "passive"))
    )
    (net (code "75") (name "unconnected-(DD10-NC-Pad11)") (class "Default")
      (node (ref "DD10") (pin "11") (pinfunction "NC_11") (pintype "passive"))
    )
    (net (code "76") (name "unconnected-(DD10-NC-Pad14)") (class "Default")
      (node (ref "DD10") (pin "14") (pinfunction "NC_14") (pintype "passive"))
    )
    (net (code "77") (name "unconnected-(DD11-NC-Pad7)") (class "Default")
      (node (ref "DD11") (pin "7") (pinfunction "NC_7") (pintype "passive"))
    )
  )
)
